# waterlevel.net
KiCad netlist of a schematic drawn in EAGLE
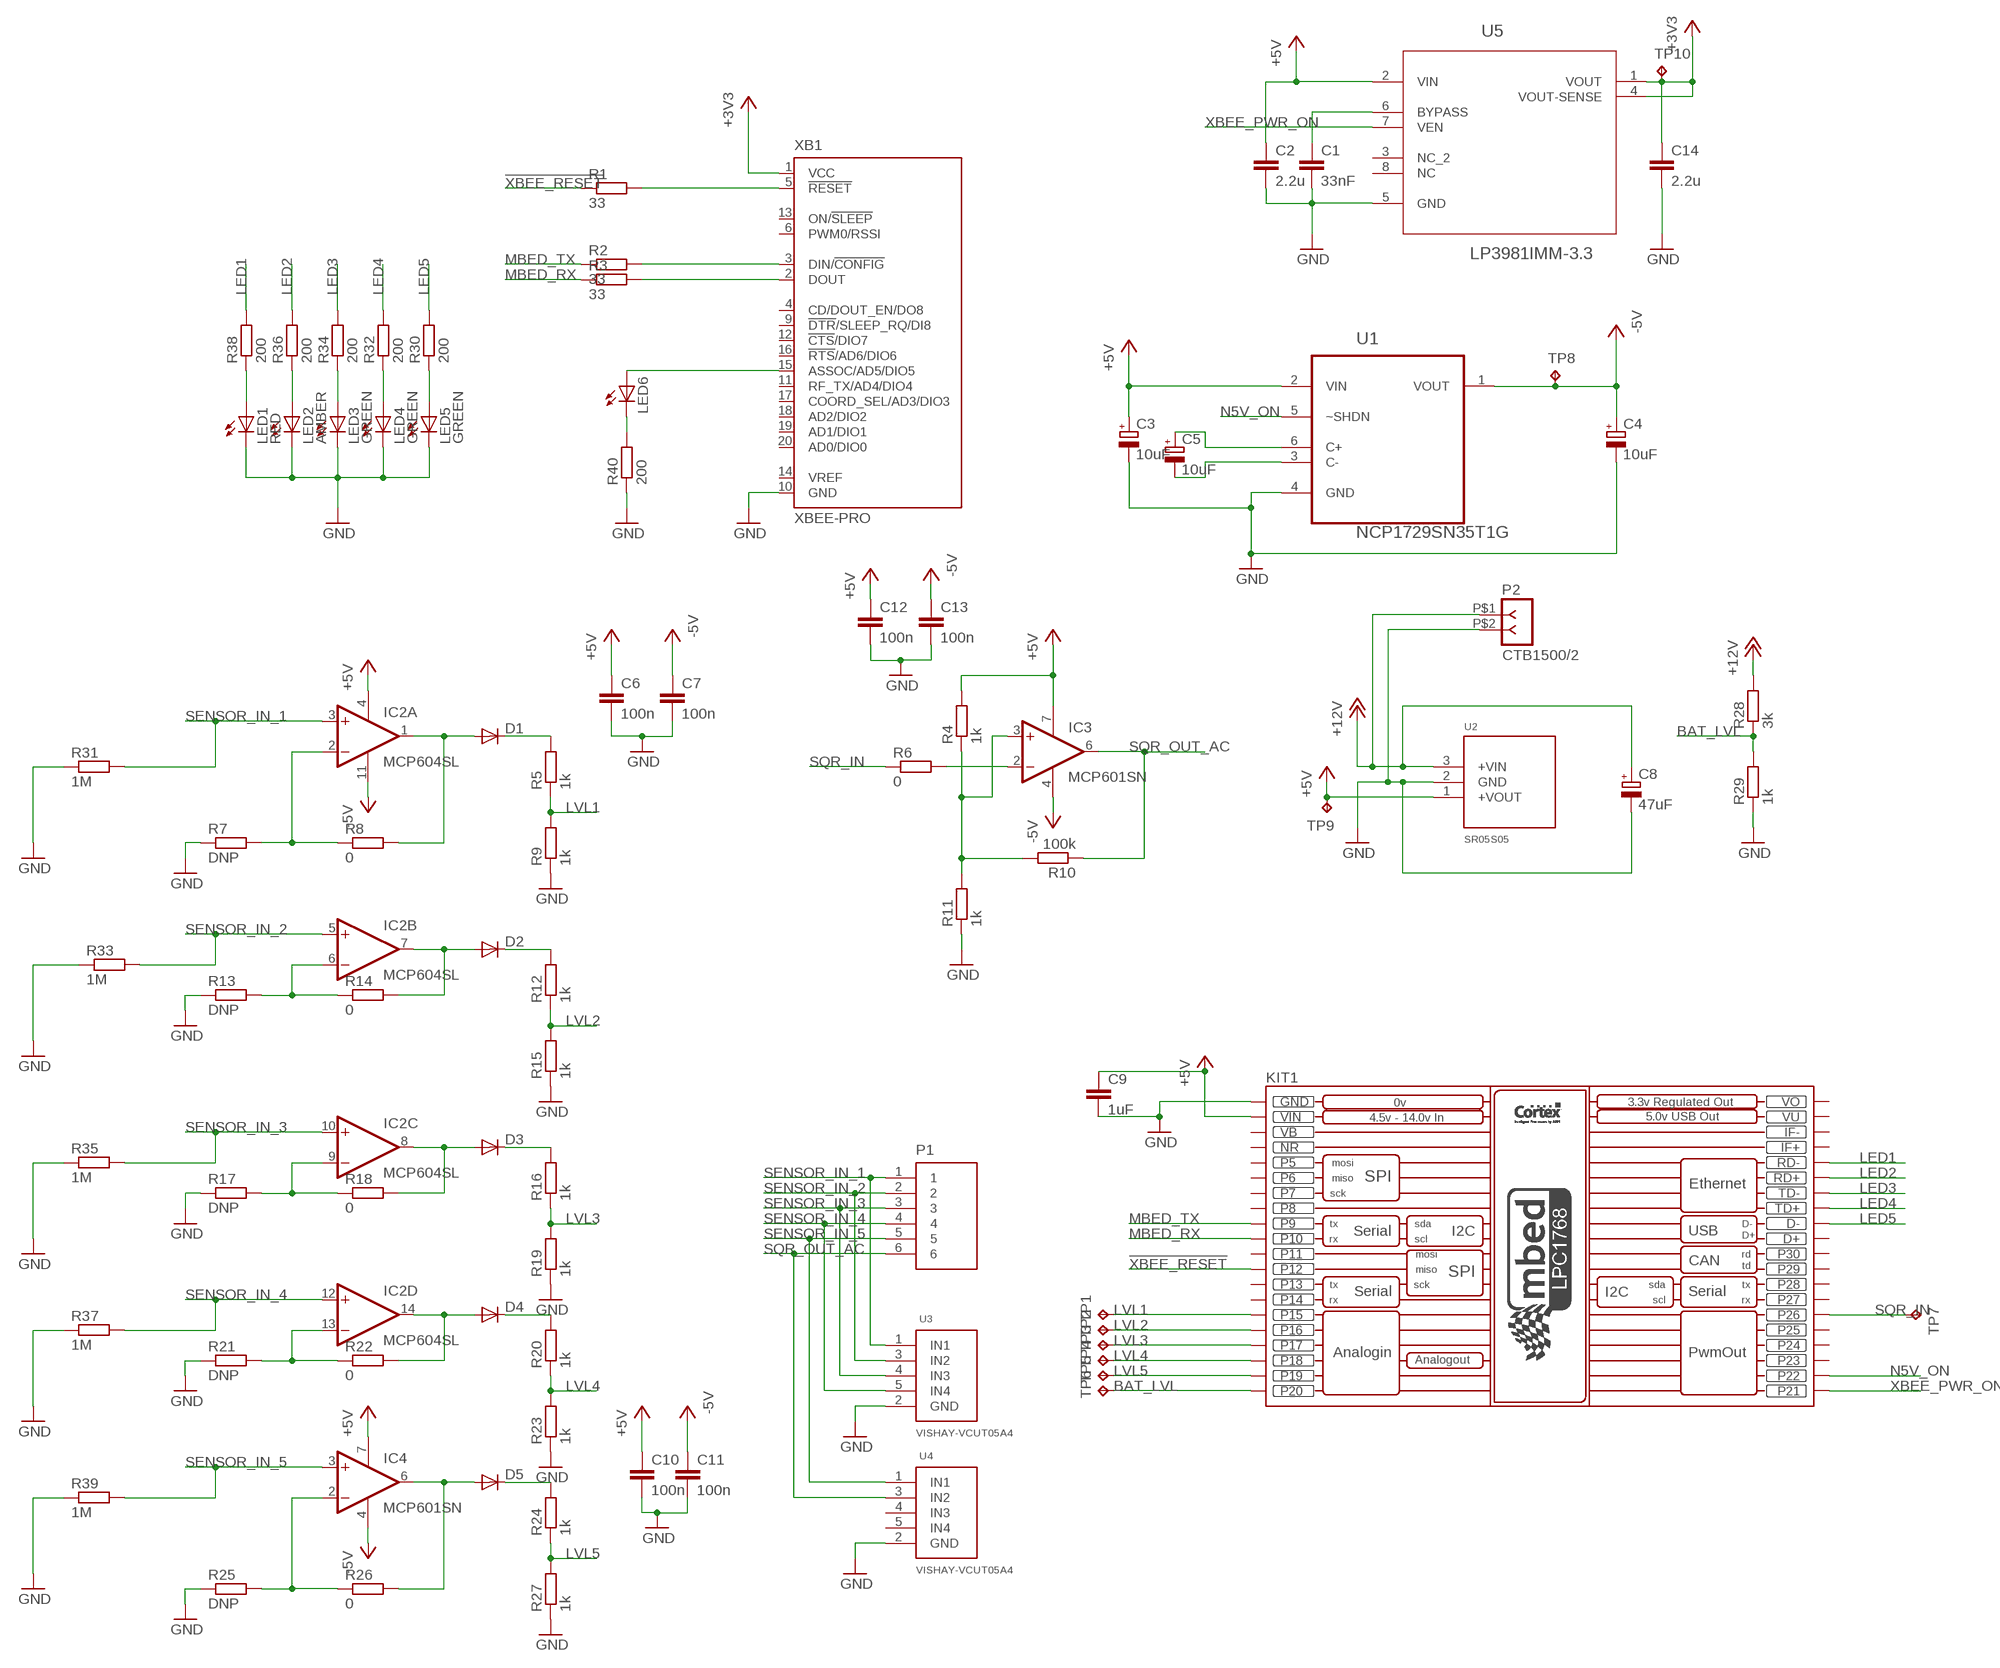
[diagram p0: schematic, sheet 1]

(export (version "E")
  (design (tool "Eeschema 10.0.6"))
  (components
    (comp (ref "C1")
      (value "33nF")
      (footprint "eagle-import:C0603")
      (libsource (lib "eagle-import") (part "C-EUC0603"))
    )
    (comp (ref "C2")
      (value "2.2u")
      (footprint "eagle-import:C0603")
      (libsource (lib "eagle-import") (part "C-EUC0603"))
    )
    (comp (ref "C3")
      (value "10uF")
      (footprint "eagle-import:D_7343-31R")
      (libsource (lib "eagle-import") (part "CPOL-EUD/7343-31R"))
    )
    (comp (ref "C4")
      (value "10uF")
      (footprint "eagle-import:D_7343-31R")
      (libsource (lib "eagle-import") (part "CPOL-EUD/7343-31R"))
    )
    (comp (ref "C5")
      (value "10uF")
      (footprint "eagle-import:D_7343-31R")
      (libsource (lib "eagle-import") (part "CPOL-EUD/7343-31R"))
    )
    (comp (ref "C6")
      (value "100n")
      (footprint "eagle-import:C1206")
      (libsource (lib "eagle-import") (part "C-EUC1206"))
    )
    (comp (ref "C7")
      (value "100n")
      (footprint "eagle-import:C1206")
      (libsource (lib "eagle-import") (part "C-EUC1206"))
    )
    (comp (ref "C8")
      (value "47uF")
      (footprint "eagle-import:D_7343-31R")
      (libsource (lib "eagle-import") (part "CPOL-EUD/7343-31R"))
    )
    (comp (ref "C9")
      (value "1uF")
      (footprint "eagle-import:C1206")
      (libsource (lib "eagle-import") (part "C-EUC1206"))
    )
    (comp (ref "C10")
      (value "100n")
      (footprint "eagle-import:C1206")
      (libsource (lib "eagle-import") (part "C-EUC1206"))
    )
    (comp (ref "C11")
      (value "100n")
      (footprint "eagle-import:C1206")
      (libsource (lib "eagle-import") (part "C-EUC1206"))
    )
    (comp (ref "C12")
      (value "100n")
      (footprint "eagle-import:C1206")
      (libsource (lib "eagle-import") (part "C-EUC1206"))
    )
    (comp (ref "C13")
      (value "100n")
      (footprint "eagle-import:C1206")
      (libsource (lib "eagle-import") (part "C-EUC1206"))
    )
    (comp (ref "C14")
      (value "2.2u")
      (footprint "eagle-import:C0603")
      (libsource (lib "eagle-import") (part "C-EUC0603"))
    )
    (comp (ref "D1")
      (value "DIODE-SOD323-R")
      (footprint "eagle-import:SOD323-R")
      (fields (field (name "PART") "RB751V40"))
      (libsource (lib "eagle-import") (part "DIODE-SOD323-R"))
    )
    (comp (ref "D2")
      (value "DIODE-SOD323-R")
      (footprint "eagle-import:SOD323-R")
      (fields (field (name "PART") "RB751V40"))
      (libsource (lib "eagle-import") (part "DIODE-SOD323-R"))
    )
    (comp (ref "D3")
      (value "DIODE-SOD323-R")
      (footprint "eagle-import:SOD323-R")
      (fields (field (name "PART") "RB751V40"))
      (libsource (lib "eagle-import") (part "DIODE-SOD323-R"))
    )
    (comp (ref "D4")
      (value "DIODE-SOD323-R")
      (footprint "eagle-import:SOD323-R")
      (fields (field (name "PART") "RB751V40"))
      (libsource (lib "eagle-import") (part "DIODE-SOD323-R"))
    )
    (comp (ref "D5")
      (value "DIODE-SOD323-R")
      (footprint "eagle-import:SOD323-R")
      (fields (field (name "PART") "RB751V40"))
      (libsource (lib "eagle-import") (part "DIODE-SOD323-R"))
    )
    (comp (ref "IC2")
      (value "MCP604SL")
      (footprint "eagle-import:SO14")
      (libsource (lib "eagle-import") (part "MCP604SL"))
    )
    (comp (ref "IC3")
      (value "MCP601SN")
      (footprint "eagle-import:SO08")
      (libsource (lib "eagle-import") (part "MCP601SN"))
    )
    (comp (ref "IC4")
      (value "MCP601SN")
      (footprint "eagle-import:SO08")
      (libsource (lib "eagle-import") (part "MCP601SN"))
    )
    (comp (ref "KIT1")
      (value "MBED_NXP_LPC1768")
      (footprint "eagle-import:MBED-KIT")
      (libsource (lib "eagle-import") (part "MBED_NXP_LPC1768"))
    )
    (comp (ref "LED1")
      (value "RED")
      (footprint "eagle-import:CHIPLED_0805")
      (libsource (lib "eagle-import") (part "LEDCHIPLED_0805"))
    )
    (comp (ref "LED2")
      (value "AMBER")
      (footprint "eagle-import:CHIPLED_0805")
      (libsource (lib "eagle-import") (part "LEDCHIPLED_0805"))
    )
    (comp (ref "LED3")
      (value "GREEN")
      (footprint "eagle-import:CHIPLED_0805")
      (libsource (lib "eagle-import") (part "LEDCHIPLED_0805"))
    )
    (comp (ref "LED4")
      (value "GREEN")
      (footprint "eagle-import:CHIPLED_0805")
      (libsource (lib "eagle-import") (part "LEDCHIPLED_0805"))
    )
    (comp (ref "LED5")
      (value "GREEN")
      (footprint "eagle-import:CHIPLED_0805")
      (libsource (lib "eagle-import") (part "LEDCHIPLED_0805"))
    )
    (comp (ref "LED6")
      (value "LEDCHIPLED_0805")
      (footprint "eagle-import:CHIPLED_0805")
      (libsource (lib "eagle-import") (part "LEDCHIPLED_0805"))
    )
    (comp (ref "P1")
      (value "CAMDEN-CTB5000/6")
      (footprint "eagle-import:CAMDEN-CTB5000")
      (libsource (lib "eagle-import") (part "CAMDEN-CTB5000/6"))
    )
    (comp (ref "P2")
      (value "CTB1500/2")
      (footprint "eagle-import:CTB1500-2")
      (libsource (lib "eagle-import") (part "CTB1500/2"))
    )
    (comp (ref "R1")
      (value "33")
      (footprint "eagle-import:R0603")
      (libsource (lib "eagle-import") (part "R-EU_R0603"))
    )
    (comp (ref "R2")
      (value "33")
      (footprint "eagle-import:R0603")
      (libsource (lib "eagle-import") (part "R-EU_R0603"))
    )
    (comp (ref "R3")
      (value "33")
      (footprint "eagle-import:R0603")
      (libsource (lib "eagle-import") (part "R-EU_R0603"))
    )
    (comp (ref "R4")
      (value "1k")
      (footprint "eagle-import:R0805")
      (libsource (lib "eagle-import") (part "R-EU_R0805"))
    )
    (comp (ref "R5")
      (value "1k")
      (footprint "eagle-import:R0805")
      (libsource (lib "eagle-import") (part "R-EU_R0805"))
    )
    (comp (ref "R6")
      (value "0")
      (footprint "eagle-import:R0603")
      (libsource (lib "eagle-import") (part "R-EU_R0603"))
    )
    (comp (ref "R7")
      (value "DNP")
      (footprint "eagle-import:R0603")
      (libsource (lib "eagle-import") (part "R-EU_R0603"))
    )
    (comp (ref "R8")
      (value "0")
      (footprint "eagle-import:R0603")
      (libsource (lib "eagle-import") (part "R-EU_R0603"))
    )
    (comp (ref "R9")
      (value "1k")
      (footprint "eagle-import:R0805")
      (libsource (lib "eagle-import") (part "R-EU_R0805"))
    )
    (comp (ref "R10")
      (value "100k")
      (footprint "eagle-import:R0805")
      (libsource (lib "eagle-import") (part "R-EU_R0805"))
    )
    (comp (ref "R11")
      (value "1k")
      (footprint "eagle-import:R0805")
      (libsource (lib "eagle-import") (part "R-EU_R0805"))
    )
    (comp (ref "R12")
      (value "1k")
      (footprint "eagle-import:R0805")
      (libsource (lib "eagle-import") (part "R-EU_R0805"))
    )
    (comp (ref "R13")
      (value "DNP")
      (footprint "eagle-import:R0603")
      (libsource (lib "eagle-import") (part "R-EU_R0603"))
    )
    (comp (ref "R14")
      (value "0")
      (footprint "eagle-import:R0603")
      (libsource (lib "eagle-import") (part "R-EU_R0603"))
    )
    (comp (ref "R15")
      (value "1k")
      (footprint "eagle-import:R0805")
      (libsource (lib "eagle-import") (part "R-EU_R0805"))
    )
    (comp (ref "R16")
      (value "1k")
      (footprint "eagle-import:R0805")
      (libsource (lib "eagle-import") (part "R-EU_R0805"))
    )
    (comp (ref "R17")
      (value "DNP")
      (footprint "eagle-import:R0603")
      (libsource (lib "eagle-import") (part "R-EU_R0603"))
    )
    (comp (ref "R18")
      (value "0")
      (footprint "eagle-import:R0603")
      (libsource (lib "eagle-import") (part "R-EU_R0603"))
    )
    (comp (ref "R19")
      (value "1k")
      (footprint "eagle-import:R0805")
      (libsource (lib "eagle-import") (part "R-EU_R0805"))
    )
    (comp (ref "R20")
      (value "1k")
      (footprint "eagle-import:R0805")
      (libsource (lib "eagle-import") (part "R-EU_R0805"))
    )
    (comp (ref "R21")
      (value "DNP")
      (footprint "eagle-import:R0603")
      (libsource (lib "eagle-import") (part "R-EU_R0603"))
    )
    (comp (ref "R22")
      (value "0")
      (footprint "eagle-import:R0603")
      (libsource (lib "eagle-import") (part "R-EU_R0603"))
    )
    (comp (ref "R23")
      (value "1k")
      (footprint "eagle-import:R0805")
      (libsource (lib "eagle-import") (part "R-EU_R0805"))
    )
    (comp (ref "R24")
      (value "1k")
      (footprint "eagle-import:R0805")
      (libsource (lib "eagle-import") (part "R-EU_R0805"))
    )
    (comp (ref "R25")
      (value "DNP")
      (footprint "eagle-import:R0603")
      (libsource (lib "eagle-import") (part "R-EU_R0603"))
    )
    (comp (ref "R26")
      (value "0")
      (footprint "eagle-import:R0603")
      (libsource (lib "eagle-import") (part "R-EU_R0603"))
    )
    (comp (ref "R27")
      (value "1k")
      (footprint "eagle-import:R0805")
      (libsource (lib "eagle-import") (part "R-EU_R0805"))
    )
    (comp (ref "R28")
      (value "3k")
      (footprint "eagle-import:R0805")
      (libsource (lib "eagle-import") (part "R-EU_R0805"))
    )
    (comp (ref "R29")
      (value "1k")
      (footprint "eagle-import:R0805")
      (libsource (lib "eagle-import") (part "R-EU_R0805"))
    )
    (comp (ref "R30")
      (value "200")
      (footprint "eagle-import:R0603")
      (libsource (lib "eagle-import") (part "R-EU_R0603"))
    )
    (comp (ref "R31")
      (value "1M")
      (footprint "eagle-import:R0805")
      (libsource (lib "eagle-import") (part "R-EU_R0805"))
    )
    (comp (ref "R32")
      (value "200")
      (footprint "eagle-import:R0603")
      (libsource (lib "eagle-import") (part "R-EU_R0603"))
    )
    (comp (ref "R33")
      (value "1M")
      (footprint "eagle-import:R0805")
      (libsource (lib "eagle-import") (part "R-EU_R0805"))
    )
    (comp (ref "R34")
      (value "200")
      (footprint "eagle-import:R0603")
      (libsource (lib "eagle-import") (part "R-EU_R0603"))
    )
    (comp (ref "R35")
      (value "1M")
      (footprint "eagle-import:R0805")
      (libsource (lib "eagle-import") (part "R-EU_R0805"))
    )
    (comp (ref "R36")
      (value "200")
      (footprint "eagle-import:R0603")
      (libsource (lib "eagle-import") (part "R-EU_R0603"))
    )
    (comp (ref "R37")
      (value "1M")
      (footprint "eagle-import:R0805")
      (libsource (lib "eagle-import") (part "R-EU_R0805"))
    )
    (comp (ref "R38")
      (value "200")
      (footprint "eagle-import:R0603")
      (libsource (lib "eagle-import") (part "R-EU_R0603"))
    )
    (comp (ref "R39")
      (value "1M")
      (footprint "eagle-import:R0805")
      (libsource (lib "eagle-import") (part "R-EU_R0805"))
    )
    (comp (ref "R40")
      (value "200")
      (footprint "eagle-import:R0603")
      (libsource (lib "eagle-import") (part "R-EU_R0603"))
    )
    (comp (ref "TP1")
      (value "TPTP13R")
      (footprint "eagle-import:TP13R")
      (libsource (lib "eagle-import") (part "TPTP13R"))
    )
    (comp (ref "TP2")
      (value "TPTP13R")
      (footprint "eagle-import:TP13R")
      (libsource (lib "eagle-import") (part "TPTP13R"))
    )
    (comp (ref "TP3")
      (value "TPTP13R")
      (footprint "eagle-import:TP13R")
      (libsource (lib "eagle-import") (part "TPTP13R"))
    )
    (comp (ref "TP4")
      (value "TPTP13R")
      (footprint "eagle-import:TP13R")
      (libsource (lib "eagle-import") (part "TPTP13R"))
    )
    (comp (ref "TP5")
      (value "TPTP13R")
      (footprint "eagle-import:TP13R")
      (libsource (lib "eagle-import") (part "TPTP13R"))
    )
    (comp (ref "TP6")
      (value "TPTP13R")
      (footprint "eagle-import:TP13R")
      (libsource (lib "eagle-import") (part "TPTP13R"))
    )
    (comp (ref "TP7")
      (value "TPTP13R")
      (footprint "eagle-import:TP13R")
      (libsource (lib "eagle-import") (part "TPTP13R"))
    )
    (comp (ref "TP8")
      (value "TPTP13R")
      (footprint "eagle-import:TP13R")
      (libsource (lib "eagle-import") (part "TPTP13R"))
    )
    (comp (ref "TP9")
      (value "TPTP13R")
      (footprint "eagle-import:TP13R")
      (libsource (lib "eagle-import") (part "TPTP13R"))
    )
    (comp (ref "TP10")
      (value "TPTP13R")
      (footprint "eagle-import:TP13R")
      (libsource (lib "eagle-import") (part "TPTP13R"))
    )
    (comp (ref "U1")
      (value "NCP1729SN35T1G")
      (footprint "eagle-import:SOP95P275X110-6N")
      (libsource (lib "eagle-import") (part "NCP1729SN35T1G"))
    )
    (comp (ref "U2")
      (value "SR05S05")
      (footprint "eagle-import:XP-SR-SERIES")
      (libsource (lib "eagle-import") (part "SR05S05"))
    )
    (comp (ref "U3")
      (value "VISHAY-VCUT05A4")
      (footprint "eagle-import:SOT23-5")
      (libsource (lib "eagle-import") (part "VISHAY-VCUT05A4"))
    )
    (comp (ref "U4")
      (value "VISHAY-VCUT05A4")
      (footprint "eagle-import:SOT23-5")
      (libsource (lib "eagle-import") (part "VISHAY-VCUT05A4"))
    )
    (comp (ref "U5")
      (value "LP3981IMM-3.3")
      (footprint "eagle-import:SOP65P490X110-8N")
      (libsource (lib "eagle-import") (part "LP3981IMM-3.3"))
    )
    (comp (ref "XB1")
      (value "XBEE-PRO")
      (footprint "eagle-import:XBEE-PRO")
      (fields (field (name "MPN") "XBP24-AWI-001"))
      (libsource (lib "eagle-import") (part "XBEE-PRO"))
    )
  )
  (nets
    (net (code "1") (name "+3V3") (class "Default")
      (node (ref "C14") (pin "1") (pinfunction "1_1") (pintype "passive"))
      (node (ref "TP10") (pin "TP") (pinfunction "TP_TP") (pintype "input"))
      (node (ref "U5") (pin "1") (pinfunction "VOUT_1") (pintype "output"))
      (node (ref "U5") (pin "4") (pinfunction "VOUT-SENSE_4") (pintype "output"))
      (node (ref "XB1") (pin "1") (pinfunction "VCC_1") (pintype "power_in"))
    )
    (net (code "2") (name "+5V") (class "Default")
      (node (ref "C10") (pin "1") (pinfunction "1_1") (pintype "passive"))
      (node (ref "C12") (pin "1") (pinfunction "1_1") (pintype "passive"))
      (node (ref "C2") (pin "1") (pinfunction "1_1") (pintype "passive"))
      (node (ref "C3") (pin "+") (pinfunction "+_+") (pintype "passive"))
      (node (ref "C6") (pin "1") (pinfunction "1_1") (pintype "passive"))
      (node (ref "C9") (pin "1") (pinfunction "1_1") (pintype "passive"))
      (node (ref "IC2") (pin "4") (pinfunction "V+_4") (pintype "power_in"))
      (node (ref "IC3") (pin "7") (pinfunction "V+_7") (pintype "power_in"))
      (node (ref "IC4") (pin "7") (pinfunction "V+_7") (pintype "power_in"))
      (node (ref "KIT1") (pin "VIN") (pinfunction "VIN_VIN") (pintype "power_in"))
      (node (ref "R4") (pin "2") (pinfunction "2_2") (pintype "passive"))
      (node (ref "TP9") (pin "TP") (pinfunction "TP_TP") (pintype "input"))
      (node (ref "U1") (pin "2") (pinfunction "VIN_2") (pintype "power_in"))
      (node (ref "U2") (pin "1") (pinfunction "+VOUT_1") (pintype "bidirectional"))
      (node (ref "U5") (pin "2") (pinfunction "VIN_2") (pintype "input"))
    )
    (net (code "3") (name "+12V") (class "Default")
      (node (ref "C8") (pin "+") (pinfunction "+_+") (pintype "passive"))
      (node (ref "P2") (pin "P$1") (pinfunction "1_P$1") (pintype "passive"))
      (node (ref "R28") (pin "2") (pinfunction "2_2") (pintype "passive"))
      (node (ref "U2") (pin "3") (pinfunction "+VIN_3") (pintype "bidirectional"))
    )
    (net (code "4") (name "-5V") (class "Default")
      (node (ref "C11") (pin "1") (pinfunction "1_1") (pintype "passive"))
      (node (ref "C13") (pin "1") (pinfunction "1_1") (pintype "passive"))
      (node (ref "C4") (pin "+") (pinfunction "+_+") (pintype "passive"))
      (node (ref "C7") (pin "1") (pinfunction "1_1") (pintype "passive"))
      (node (ref "IC2") (pin "11") (pinfunction "V-_11") (pintype "power_in"))
      (node (ref "IC3") (pin "4") (pinfunction "V-_4") (pintype "power_in"))
      (node (ref "IC4") (pin "4") (pinfunction "V-_4") (pintype "power_in"))
      (node (ref "TP8") (pin "TP") (pinfunction "TP_TP") (pintype "input"))
      (node (ref "U1") (pin "1") (pinfunction "VOUT_1") (pintype "output"))
    )
    (net (code "5") (name "/BAT_LVL") (class "Default")
      (node (ref "KIT1") (pin "P$20") (pinfunction "P20_P$20") (pintype "bidirectional"))
      (node (ref "R28") (pin "1") (pinfunction "1_1") (pintype "passive"))
      (node (ref "R29") (pin "2") (pinfunction "2_2") (pintype "passive"))
      (node (ref "TP6") (pin "TP") (pinfunction "TP_TP") (pintype "input"))
    )
    (net (code "6") (name "/LED1") (class "Default")
      (node (ref "KIT1") (pin "RD-") (pinfunction "RD-_RD-") (pintype "bidirectional"))
      (node (ref "R38") (pin "2") (pinfunction "2_2") (pintype "passive"))
    )
    (net (code "7") (name "/LED2") (class "Default")
      (node (ref "KIT1") (pin "RD+") (pinfunction "RD+_RD+") (pintype "bidirectional"))
      (node (ref "R36") (pin "2") (pinfunction "2_2") (pintype "passive"))
    )
    (net (code "8") (name "/LED3") (class "Default")
      (node (ref "KIT1") (pin "TD-") (pinfunction "TD-_TD-") (pintype "bidirectional"))
      (node (ref "R34") (pin "2") (pinfunction "2_2") (pintype "passive"))
    )
    (net (code "9") (name "/LED4") (class "Default")
      (node (ref "KIT1") (pin "TD+") (pinfunction "TD+_TD+") (pintype "bidirectional"))
      (node (ref "R32") (pin "2") (pinfunction "2_2") (pintype "passive"))
    )
    (net (code "10") (name "/LED5") (class "Default")
      (node (ref "KIT1") (pin "D-") (pinfunction "D-_D-") (pintype "bidirectional"))
      (node (ref "R30") (pin "2") (pinfunction "2_2") (pintype "passive"))
    )
    (net (code "11") (name "/LVL1") (class "Default")
      (node (ref "KIT1") (pin "P$15") (pinfunction "P15_P$15") (pintype "bidirectional"))
      (node (ref "R5") (pin "1") (pinfunction "1_1") (pintype "passive"))
      (node (ref "R9") (pin "2") (pinfunction "2_2") (pintype "passive"))
      (node (ref "TP1") (pin "TP") (pinfunction "TP_TP") (pintype "input"))
    )
    (net (code "12") (name "/LVL2") (class "Default")
      (node (ref "KIT1") (pin "P$16") (pinfunction "P16_P$16") (pintype "bidirectional"))
      (node (ref "R12") (pin "1") (pinfunction "1_1") (pintype "passive"))
      (node (ref "R15") (pin "2") (pinfunction "2_2") (pintype "passive"))
      (node (ref "TP2") (pin "TP") (pinfunction "TP_TP") (pintype "input"))
    )
    (net (code "13") (name "/LVL3") (class "Default")
      (node (ref "KIT1") (pin "P$17") (pinfunction "P17_P$17") (pintype "bidirectional"))
      (node (ref "R16") (pin "1") (pinfunction "1_1") (pintype "passive"))
      (node (ref "R19") (pin "2") (pinfunction "2_2") (pintype "passive"))
      (node (ref "TP3") (pin "TP") (pinfunction "TP_TP") (pintype "input"))
    )
    (net (code "14") (name "/LVL4") (class "Default")
      (node (ref "KIT1") (pin "P$18") (pinfunction "P18_P$18") (pintype "bidirectional"))
      (node (ref "R20") (pin "1") (pinfunction "1_1") (pintype "passive"))
      (node (ref "R23") (pin "2") (pinfunction "2_2") (pintype "passive"))
      (node (ref "TP4") (pin "TP") (pinfunction "TP_TP") (pintype "input"))
    )
    (net (code "15") (name "/LVL5") (class "Default")
      (node (ref "KIT1") (pin "P$19") (pinfunction "P19_P$19") (pintype "bidirectional"))
      (node (ref "R24") (pin "1") (pinfunction "1_1") (pintype "passive"))
      (node (ref "R27") (pin "2") (pinfunction "2_2") (pintype "passive"))
      (node (ref "TP5") (pin "TP") (pinfunction "TP_TP") (pintype "input"))
    )
    (net (code "16") (name "/MBED_RX") (class "Default")
      (node (ref "KIT1") (pin "P$10") (pinfunction "P10_P$10") (pintype "bidirectional"))
      (node (ref "R3") (pin "1") (pinfunction "1_1") (pintype "passive"))
    )
    (net (code "17") (name "/MBED_TX") (class "Default")
      (node (ref "KIT1") (pin "P$9") (pinfunction "P9_P$9") (pintype "bidirectional"))
      (node (ref "R2") (pin "1") (pinfunction "1_1") (pintype "passive"))
    )
    (net (code "18") (name "/N5V_ON") (class "Default")
      (node (ref "KIT1") (pin "P$22") (pinfunction "P22_P$22") (pintype "bidirectional"))
      (node (ref "U1") (pin "5") (pinfunction "~{SHDN}_5") (pintype "input"))
    )
    (net (code "19") (name "/NR") (class "Default")
      (node (ref "KIT1") (pin "NR") (pinfunction "NR_NR") (pintype "power_in"))
    )
    (net (code "20") (name "/SENSOR_IN_1") (class "Default")
      (node (ref "IC2") (pin "3") (pinfunction "+IN_3") (pintype "input"))
      (node (ref "P1") (pin "1") (pinfunction "1_1") (pintype "bidirectional"))
      (node (ref "R31") (pin "2") (pinfunction "2_2") (pintype "passive"))
      (node (ref "U3") (pin "1") (pinfunction "IN1_1") (pintype "bidirectional"))
    )
    (net (code "21") (name "/SENSOR_IN_2") (class "Default")
      (node (ref "IC2") (pin "5") (pinfunction "+IN_5") (pintype "input"))
      (node (ref "P1") (pin "2") (pinfunction "2_2") (pintype "bidirectional"))
      (node (ref "R33") (pin "2") (pinfunction "2_2") (pintype "passive"))
      (node (ref "U3") (pin "3") (pinfunction "IN2_3") (pintype "bidirectional"))
    )
    (net (code "22") (name "/SENSOR_IN_3") (class "Default")
      (node (ref "IC2") (pin "10") (pinfunction "+IN_10") (pintype "input"))
      (node (ref "P1") (pin "3") (pinfunction "3_3") (pintype "bidirectional"))
      (node (ref "R35") (pin "2") (pinfunction "2_2") (pintype "passive"))
      (node (ref "U3") (pin "4") (pinfunction "IN3_4") (pintype "bidirectional"))
    )
    (net (code "23") (name "/SENSOR_IN_4") (class "Default")
      (node (ref "IC2") (pin "12") (pinfunction "+IN_12") (pintype "input"))
      (node (ref "P1") (pin "4") (pinfunction "4_4") (pintype "bidirectional"))
      (node (ref "R37") (pin "2") (pinfunction "2_2") (pintype "passive"))
      (node (ref "U3") (pin "5") (pinfunction "IN4_5") (pintype "bidirectional"))
    )
    (net (code "24") (name "/SENSOR_IN_5") (class "Default")
      (node (ref "IC4") (pin "3") (pinfunction "+IN_3") (pintype "input"))
      (node (ref "P1") (pin "5") (pinfunction "5_5") (pintype "bidirectional"))
      (node (ref "R39") (pin "2") (pinfunction "2_2") (pintype "passive"))
      (node (ref "U4") (pin "1") (pinfunction "IN1_1") (pintype "bidirectional"))
    )
    (net (code "25") (name "/SQR_IN") (class "Default")
      (node (ref "KIT1") (pin "P$26") (pinfunction "P26_P$26") (pintype "bidirectional"))
      (node (ref "R6") (pin "1") (pinfunction "1_1") (pintype "passive"))
      (node (ref "TP7") (pin "TP") (pinfunction "TP_TP") (pintype "input"))
    )
    (net (code "26") (name "/SQR_OUT_AC") (class "Default")
      (node (ref "IC3") (pin "6") (pinfunction "OUT_6") (pintype "output"))
      (node (ref "P1") (pin "6") (pinfunction "6_6") (pintype "bidirectional"))
      (node (ref "R10") (pin "1") (pinfunction "1_1") (pintype "passive"))
      (node (ref "U4") (pin "3") (pinfunction "IN2_3") (pintype "bidirectional"))
    )
    (net (code "27") (name "/VB") (class "Default")
      (node (ref "KIT1") (pin "VB") (pinfunction "VB_VB") (pintype "power_in"))
    )
    (net (code "28") (name "/VO") (class "Default")
      (node (ref "KIT1") (pin "VOUT") (pinfunction "VO_VOUT") (pintype "power_in"))
    )
    (net (code "29") (name "/VU") (class "Default")
      (node (ref "KIT1") (pin "VU") (pinfunction "VU_VU") (pintype "power_in"))
    )
    (net (code "30") (name "/XBEE_PWR_ON") (class "Default")
      (node (ref "KIT1") (pin "P$21") (pinfunction "P21_P$21") (pintype "bidirectional"))
      (node (ref "U5") (pin "7") (pinfunction "VEN_7") (pintype "input"))
    )
    (net (code "31") (name "/~{XBEE_RESET}") (class "Default")
      (node (ref "KIT1") (pin "P$12") (pinfunction "P12_P$12") (pintype "bidirectional"))
      (node (ref "R1") (pin "1") (pinfunction "1_1") (pintype "passive"))
    )
    (net (code "32") (name "GND") (class "Default")
      (node (ref "C1") (pin "2") (pinfunction "2_2") (pintype "passive"))
      (node (ref "C10") (pin "2") (pinfunction "2_2") (pintype "passive"))
      (node (ref "C11") (pin "2") (pinfunction "2_2") (pintype "passive"))
      (node (ref "C12") (pin "2") (pinfunction "2_2") (pintype "passive"))
      (node (ref "C13") (pin "2") (pinfunction "2_2") (pintype "passive"))
      (node (ref "C14") (pin "2") (pinfunction "2_2") (pintype "passive"))
      (node (ref "C2") (pin "2") (pinfunction "2_2") (pintype "passive"))
      (node (ref "C3") (pin "-") (pinfunction "-_-") (pintype "passive"))
      (node (ref "C4") (pin "-") (pinfunction "-_-") (pintype "passive"))
      (node (ref "C6") (pin "2") (pinfunction "2_2") (pintype "passive"))
      (node (ref "C7") (pin "2") (pinfunction "2_2") (pintype "passive"))
      (node (ref "C8") (pin "-") (pinfunction "-_-") (pintype "passive"))
      (node (ref "C9") (pin "2") (pinfunction "2_2") (pintype "passive"))
      (node (ref "KIT1") (pin "GND") (pinfunction "GND_GND") (pintype "power_in"))
      (node (ref "LED1") (pin "C") (pinfunction "C_C") (pintype "passive"))
      (node (ref "LED2") (pin "C") (pinfunction "C_C") (pintype "passive"))
      (node (ref "LED3") (pin "C") (pinfunction "C_C") (pintype "passive"))
      (node (ref "LED4") (pin "C") (pinfunction "C_C") (pintype "passive"))
      (node (ref "LED5") (pin "C") (pinfunction "C_C") (pintype "passive"))
      (node (ref "P2") (pin "P$2") (pinfunction "2_P$2") (pintype "passive"))
      (node (ref "R11") (pin "1") (pinfunction "1_1") (pintype "passive"))
      (node (ref "R13") (pin "1") (pinfunction "1_1") (pintype "passive"))
      (node (ref "R15") (pin "1") (pinfunction "1_1") (pintype "passive"))
      (node (ref "R17") (pin "1") (pinfunction "1_1") (pintype "passive"))
      (node (ref "R19") (pin "1") (pinfunction "1_1") (pintype "passive"))
      (node (ref "R21") (pin "1") (pinfunction "1_1") (pintype "passive"))
      (node (ref "R23") (pin "1") (pinfunction "1_1") (pintype "passive"))
      (node (ref "R25") (pin "1") (pinfunction "1_1") (pintype "passive"))
      (node (ref "R27") (pin "1") (pinfunction "1_1") (pintype "passive"))
      (node (ref "R29") (pin "1") (pinfunction "1_1") (pintype "passive"))
      (node (ref "R31") (pin "1") (pinfunction "1_1") (pintype "passive"))
      (node (ref "R33") (pin "1") (pinfunction "1_1") (pintype "passive"))
      (node (ref "R35") (pin "1") (pinfunction "1_1") (pintype "passive"))
      (node (ref "R37") (pin "1") (pinfunction "1_1") (pintype "passive"))
      (node (ref "R39") (pin "1") (pinfunction "1_1") (pintype "passive"))
      (node (ref "R40") (pin "1") (pinfunction "1_1") (pintype "passive"))
      (node (ref "R7") (pin "1") (pinfunction "1_1") (pintype "passive"))
      (node (ref "R9") (pin "1") (pinfunction "1_1") (pintype "passive"))
      (node (ref "U1") (pin "4") (pinfunction "GND_4") (pintype "passive"))
      (node (ref "U2") (pin "2") (pinfunction "GND_2") (pintype "bidirectional"))
      (node (ref "U3") (pin "2") (pinfunction "GND_2") (pintype "bidirectional"))
      (node (ref "U4") (pin "2") (pinfunction "GND_2") (pintype "bidirectional"))
      (node (ref "U5") (pin "5") (pinfunction "GND_5") (pintype "passive"))
      (node (ref "XB1") (pin "10") (pinfunction "GND_10") (pintype "power_in"))
    )
    (net (code "33") (name "Net-(D1-PadC)") (class "Default")
      (node (ref "D1") (pin "C") (pinfunction "C_C") (pintype "passive"))
      (node (ref "R5") (pin "2") (pinfunction "2_2") (pintype "passive"))
    )
    (net (code "34") (name "Net-(D2-PadC)") (class "Default")
      (node (ref "D2") (pin "C") (pinfunction "C_C") (pintype "passive"))
      (node (ref "R12") (pin "2") (pinfunction "2_2") (pintype "passive"))
    )
    (net (code "35") (name "Net-(D3-PadC)") (class "Default")
      (node (ref "D3") (pin "C") (pinfunction "C_C") (pintype "passive"))
      (node (ref "R16") (pin "2") (pinfunction "2_2") (pintype "passive"))
    )
    (net (code "36") (name "Net-(D4-PadC)") (class "Default")
      (node (ref "D4") (pin "C") (pinfunction "C_C") (pintype "passive"))
      (node (ref "R20") (pin "2") (pinfunction "2_2") (pintype "passive"))
    )
    (net (code "37") (name "Net-(D5-PadC)") (class "Default")
      (node (ref "D5") (pin "C") (pinfunction "C_C") (pintype "passive"))
      (node (ref "R24") (pin "2") (pinfunction "2_2") (pintype "passive"))
    )
    (net (code "38") (name "Net-(IC2A--IN)") (class "Default")
      (node (ref "IC2") (pin "2") (pinfunction "-IN_2") (pintype "input"))
      (node (ref "R7") (pin "2") (pinfunction "2_2") (pintype "passive"))
      (node (ref "R8") (pin "1") (pinfunction "1_1") (pintype "passive"))
    )
    (net (code "39") (name "Net-(IC2A-OUT)") (class "Default")
      (node (ref "D1") (pin "A") (pinfunction "A_A") (pintype "passive"))
      (node (ref "IC2") (pin "1") (pinfunction "OUT_1") (pintype "output"))
      (node (ref "R8") (pin "2") (pinfunction "2_2") (pintype "passive"))
    )
    (net (code "40") (name "Net-(IC2B--IN)") (class "Default")
      (node (ref "IC2") (pin "6") (pinfunction "-IN_6") (pintype "input"))
      (node (ref "R13") (pin "2") (pinfunction "2_2") (pintype "passive"))
      (node (ref "R14") (pin "1") (pinfunction "1_1") (pintype "passive"))
    )
    (net (code "41") (name "Net-(IC2B-OUT)") (class "Default")
      (node (ref "D2") (pin "A") (pinfunction "A_A") (pintype "passive"))
      (node (ref "IC2") (pin "7") (pinfunction "OUT_7") (pintype "output"))
      (node (ref "R14") (pin "2") (pinfunction "2_2") (pintype "passive"))
    )
    (net (code "42") (name "Net-(IC2C--IN)") (class "Default")
      (node (ref "IC2") (pin "9") (pinfunction "-IN_9") (pintype "input"))
      (node (ref "R17") (pin "2") (pinfunction "2_2") (pintype "passive"))
      (node (ref "R18") (pin "1") (pinfunction "1_1") (pintype "passive"))
    )
    (net (code "43") (name "Net-(IC2C-OUT)") (class "Default")
      (node (ref "D3") (pin "A") (pinfunction "A_A") (pintype "passive"))
      (node (ref "IC2") (pin "8") (pinfunction "OUT_8") (pintype "output"))
      (node (ref "R18") (pin "2") (pinfunction "2_2") (pintype "passive"))
    )
    (net (code "44") (name "Net-(IC2D--IN)") (class "Default")
      (node (ref "IC2") (pin "13") (pinfunction "-IN_13") (pintype "input"))
      (node (ref "R21") (pin "2") (pinfunction "2_2") (pintype "passive"))
      (node (ref "R22") (pin "1") (pinfunction "1_1") (pintype "passive"))
    )
    (net (code "45") (name "Net-(IC2D-OUT)") (class "Default")
      (node (ref "D4") (pin "A") (pinfunction "A_A") (pintype "passive"))
      (node (ref "IC2") (pin "14") (pinfunction "OUT_14") (pintype "output"))
      (node (ref "R22") (pin "2") (pinfunction "2_2") (pintype "passive"))
    )
    (net (code "46") (name "Net-(IC3-+IN)") (class "Default")
      (node (ref "IC3") (pin "3") (pinfunction "+IN_3") (pintype "input"))
      (node (ref "R10") (pin "2") (pinfunction "2_2") (pintype "passive"))
      (node (ref "R11") (pin "2") (pinfunction "2_2") (pintype "passive"))
      (node (ref "R4") (pin "1") (pinfunction "1_1") (pintype "passive"))
    )
    (net (code "47") (name "Net-(IC3--IN)") (class "Default")
      (node (ref "IC3") (pin "2") (pinfunction "-IN_2") (pintype "input"))
      (node (ref "R6") (pin "2") (pinfunction "2_2") (pintype "passive"))
    )
    (net (code "48") (name "Net-(IC4--IN)") (class "Default")
      (node (ref "IC4") (pin "2") (pinfunction "-IN_2") (pintype "input"))
      (node (ref "R25") (pin "2") (pinfunction "2_2") (pintype "passive"))
      (node (ref "R26") (pin "1") (pinfunction "1_1") (pintype "passive"))
    )
    (net (code "49") (name "Net-(IC4-OUT)") (class "Default")
      (node (ref "D5") (pin "A") (pinfunction "A_A") (pintype "passive"))
      (node (ref "IC4") (pin "6") (pinfunction "OUT_6") (pintype "output"))
      (node (ref "R26") (pin "2") (pinfunction "2_2") (pintype "passive"))
    )
    (net (code "50") (name "Net-(LED1-PadA)") (class "Default")
      (node (ref "LED1") (pin "A") (pinfunction "A_A") (pintype "passive"))
      (node (ref "R38") (pin "1") (pinfunction "1_1") (pintype "passive"))
    )
    (net (code "51") (name "Net-(LED2-PadA)") (class "Default")
      (node (ref "LED2") (pin "A") (pinfunction "A_A") (pintype "passive"))
      (node (ref "R36") (pin "1") (pinfunction "1_1") (pintype "passive"))
    )
    (net (code "52") (name "Net-(LED3-PadA)") (class "Default")
      (node (ref "LED3") (pin "A") (pinfunction "A_A") (pintype "passive"))
      (node (ref "R34") (pin "1") (pinfunction "1_1") (pintype "passive"))
    )
    (net (code "53") (name "Net-(LED4-PadA)") (class "Default")
      (node (ref "LED4") (pin "A") (pinfunction "A_A") (pintype "passive"))
      (node (ref "R32") (pin "1") (pinfunction "1_1") (pintype "passive"))
    )
    (net (code "54") (name "Net-(LED5-PadA)") (class "Default")
      (node (ref "LED5") (pin "A") (pinfunction "A_A") (pintype "passive"))
      (node (ref "R30") (pin "1") (pinfunction "1_1") (pintype "passive"))
    )
    (net (code "55") (name "Net-(LED6-PadC)") (class "Default")
      (node (ref "LED6") (pin "C") (pinfunction "C_C") (pintype "passive"))
      (node (ref "R40") (pin "2") (pinfunction "2_2") (pintype "passive"))
    )
    (net (code "56") (name "Net-(U1-C+)") (class "Default")
      (node (ref "C5") (pin "+") (pinfunction "+_+") (pintype "passive"))
      (node (ref "U1") (pin "6") (pinfunction "C+_6") (pintype "passive"))
    )
    (net (code "57") (name "Net-(U1-C-)") (class "Default")
      (node (ref "C5") (pin "-") (pinfunction "-_-") (pintype "passive"))
      (node (ref "U1") (pin "3") (pinfunction "C-_3") (pintype "passive"))
    )
    (net (code "58") (name "Net-(U5-BYPASS)") (class "Default")
      (node (ref "C1") (pin "1") (pinfunction "1_1") (pintype "passive"))
      (node (ref "U5") (pin "6") (pinfunction "BYPASS_6") (pintype "input"))
    )
    (net (code "59") (name "Net-(XB1-ASSOC{slash}AD5{slash}DIO5)") (class "Default")
      (node (ref "LED6") (pin "A") (pinfunction "A_A") (pintype "passive"))
      (node (ref "XB1") (pin "15") (pinfunction "ASSOC/AD5/DIO5_15") (pintype "bidirectional"))
    )
    (net (code "60") (name "Net-(XB1-DIN{slash}~{CONFIG})") (class "Default")
      (node (ref "R2") (pin "2") (pinfunction "2_2") (pintype "passive"))
      (node (ref "XB1") (pin "3") (pinfunction "DIN/~{CONFIG}_3") (pintype "input"))
    )
    (net (code "61") (name "Net-(XB1-DOUT)") (class "Default")
      (node (ref "R3") (pin "2") (pinfunction "2_2") (pintype "passive"))
      (node (ref "XB1") (pin "2") (pinfunction "DOUT_2") (pintype "output"))
    )
    (net (code "62") (name "Net-(XB1-~{RESET})") (class "Default")
      (node (ref "R1") (pin "2") (pinfunction "2_2") (pintype "passive"))
      (node (ref "XB1") (pin "5") (pinfunction "~{RESET}_5") (pintype "input"))
    )
    (net (code "63") (name "unconnected-(KIT1-P5-PadP$5)") (class "Default")
      (node (ref "KIT1") (pin "P$5") (pinfunction "P5_P$5") (pintype "bidirectional"))
    )
    (net (code "64") (name "unconnected-(KIT1-P6-PadP$6)") (class "Default")
      (node (ref "KIT1") (pin "P$6") (pinfunction "P6_P$6") (pintype "bidirectional"))
    )
    (net (code "65") (name "unconnected-(KIT1-P7-PadP$7)") (class "Default")
      (node (ref "KIT1") (pin "P$7") (pinfunction "P7_P$7") (pintype "bidirectional"))
    )
    (net (code "66") (name "unconnected-(KIT1-P8-PadP$8)") (class "Default")
      (node (ref "KIT1") (pin "P$8") (pinfunction "P8_P$8") (pintype "bidirectional"))
    )
    (net (code "67") (name "unconnected-(KIT1-P11-PadP$11)") (class "Default")
      (node (ref "KIT1") (pin "P$11") (pinfunction "P11_P$11") (pintype "bidirectional"))
    )
    (net (code "68") (name "unconnected-(KIT1-P13-PadP$13)") (class "Default")
      (node (ref "KIT1") (pin "P$13") (pinfunction "P13_P$13") (pintype "bidirectional"))
    )
    (net (code "69") (name "unconnected-(KIT1-P14-PadP$14)") (class "Default")
      (node (ref "KIT1") (pin "P$14") (pinfunction "P14_P$14") (pintype "bidirectional"))
    )
    (net (code "70") (name "unconnected-(KIT1-P23-PadP$23)") (class "Default")
      (node (ref "KIT1") (pin "P$23") (pinfunction "P23_P$23") (pintype "bidirectional"))
    )
    (net (code "71") (name "unconnected-(KIT1-P24-PadP$24)") (class "Default")
      (node (ref "KIT1") (pin "P$24") (pinfunction "P24_P$24") (pintype "bidirectional"))
    )
    (net (code "72") (name "unconnected-(KIT1-P25-PadP$25)") (class "Default")
      (node (ref "KIT1") (pin "P$25") (pinfunction "P25_P$25") (pintype "bidirectional"))
    )
    (net (code "73") (name "unconnected-(KIT1-P27-PadP$27)") (class "Default")
      (node (ref "KIT1") (pin "P$27") (pinfunction "P27_P$27") (pintype "bidirectional"))
    )
    (net (code "74") (name "unconnected-(KIT1-P28-PadP$28)") (class "Default")
      (node (ref "KIT1") (pin "P$28") (pinfunction "P28_P$28") (pintype "bidirectional"))
    )
    (net (code "75") (name "unconnected-(KIT1-P29-PadP$29)") (class "Default")
      (node (ref "KIT1") (pin "P$29") (pinfunction "P29_P$29") (pintype "bidirectional"))
    )
    (net (code "76") (name "unconnected-(KIT1-P30-PadP$30)") (class "Default")
      (node (ref "KIT1") (pin "P$30") (pinfunction "P30_P$30") (pintype "bidirectional"))
    )
    (net (code "77") (name "unconnected-(KIT1-PadD+)") (class "Default")
      (node (ref "KIT1") (pin "D+") (pinfunction "D+_D+") (pintype "bidirectional"))
    )
    (net (code "78") (name "unconnected-(KIT1-PadIF+)") (class "Default")
      (node (ref "KIT1") (pin "IF+") (pinfunction "IF+_IF+") (pintype "bidirectional"))
    )
    (net (code "79") (name "unconnected-(KIT1-PadIF-)") (class "Default")
      (node (ref "KIT1") (pin "IF-") (pinfunction "IF-_IF-") (pintype "bidirectional"))
    )
    (net (code "80") (name "unconnected-(U4-IN3-Pad4)") (class "Default")
      (node (ref "U4") (pin "4") (pinfunction "IN3_4") (pintype "bidirectional"))
    )
    (net (code "81") (name "unconnected-(U4-IN4-Pad5)") (class "Default")
      (node (ref "U4") (pin "5") (pinfunction "IN4_5") (pintype "bidirectional"))
    )
    (net (code "82") (name "unconnected-(U5-NC-Pad8)") (class "Default")
      (node (ref "U5") (pin "8") (pinfunction "NC_8") (pintype "no_connect"))
    )
    (net (code "83") (name "unconnected-(U5-NC_2-Pad3)") (class "Default")
      (node (ref "U5") (pin "3") (pinfunction "NC_2_3") (pintype "no_connect"))
    )
    (net (code "84") (name "unconnected-(XB1-AD0{slash}DIO0-Pad20)") (class "Default")
      (node (ref "XB1") (pin "20") (pinfunction "AD0/DIO0_20") (pintype "bidirectional"))
    )
    (net (code "85") (name "unconnected-(XB1-AD1{slash}DIO1-Pad19)") (class "Default")
      (node (ref "XB1") (pin "19") (pinfunction "AD1/DIO1_19") (pintype "bidirectional"))
    )
    (net (code "86") (name "unconnected-(XB1-AD2{slash}DIO2-Pad18)") (class "Default")
      (node (ref "XB1") (pin "18") (pinfunction "AD2/DIO2_18") (pintype "bidirectional"))
    )
    (net (code "87") (name "unconnected-(XB1-CD{slash}DOUT_EN{slash}DO8-Pad4)") (class "Default")
      (node (ref "XB1") (pin "4") (pinfunction "CD/DOUT_EN/DO8_4") (pintype "output"))
    )
    (net (code "88") (name "unconnected-(XB1-COORD_SEL{slash}AD3{slash}DIO3-Pad17)") (class "Default")
      (node (ref "XB1") (pin "17") (pinfunction "COORD_SEL/AD3/DIO3_17") (pintype "bidirectional"))
    )
    (net (code "89") (name "unconnected-(XB1-ON{slash}~{SLEEP}-Pad13)") (class "Default")
      (node (ref "XB1") (pin "13") (pinfunction "ON/~{SLEEP}_13") (pintype "output"))
    )
    (net (code "90") (name "unconnected-(XB1-PWM0{slash}RSSI-Pad6)") (class "Default")
      (node (ref "XB1") (pin "6") (pinfunction "PWM0/RSSI_6") (pintype "output"))
    )
    (net (code "91") (name "unconnected-(XB1-RF_TX{slash}AD4{slash}DIO4-Pad11)") (class "Default")
      (node (ref "XB1") (pin "11") (pinfunction "RF_TX/AD4/DIO4_11") (pintype "bidirectional"))
    )
    (net (code "92") (name "unconnected-(XB1-VREF-Pad14)") (class "Default")
      (node (ref "XB1") (pin "14") (pinfunction "VREF_14") (pintype "input"))
    )
    (net (code "93") (name "unconnected-(XB1-~{CTS}{slash}DIO7-Pad12)") (class "Default")
      (node (ref "XB1") (pin "12") (pinfunction "~{CTS}/DIO7_12") (pintype "bidirectional"))
    )
    (net (code "94") (name "unconnected-(XB1-~{DTR}{slash}SLEEP_RQ{slash}DI8-Pad9)") (class "Default")
      (node (ref "XB1") (pin "9") (pinfunction "~{DTR}/SLEEP_RQ/DI8_9") (pintype "bidirectional"))
    )
    (net (code "95") (name "unconnected-(XB1-~{RTS}{slash}AD6{slash}DIO6-Pad16)") (class "Default")
      (node (ref "XB1") (pin "16") (pinfunction "~{RTS}/AD6/DIO6_16") (pintype "bidirectional"))
    )
  )
)
